# watCals_schmatic.net
KiCad netlist of a schematic drawn in EAGLE
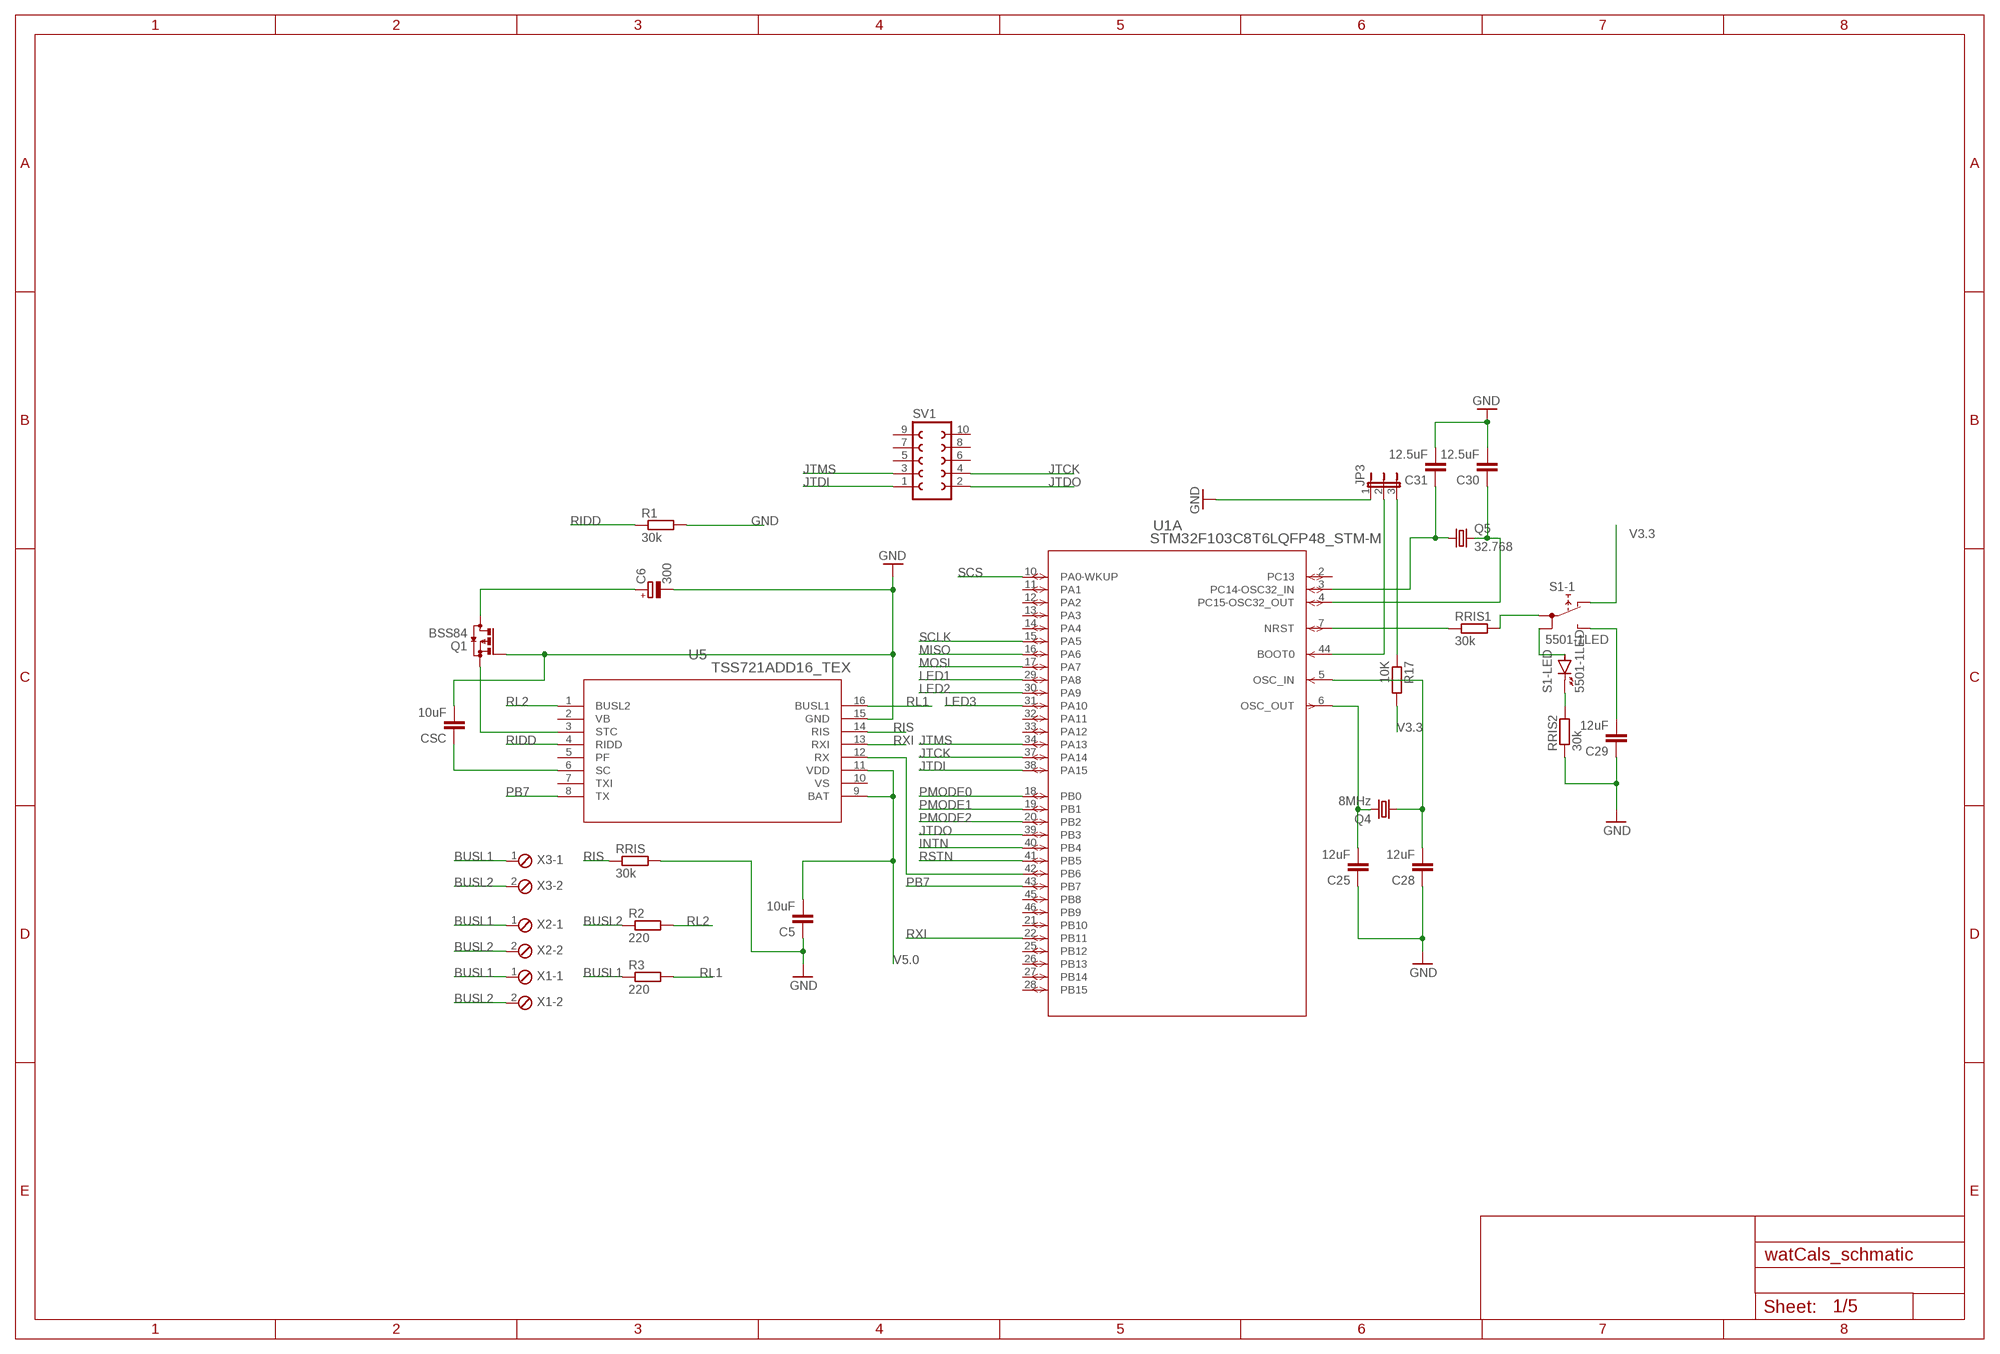
[diagram p0: schematic, sheet 1]
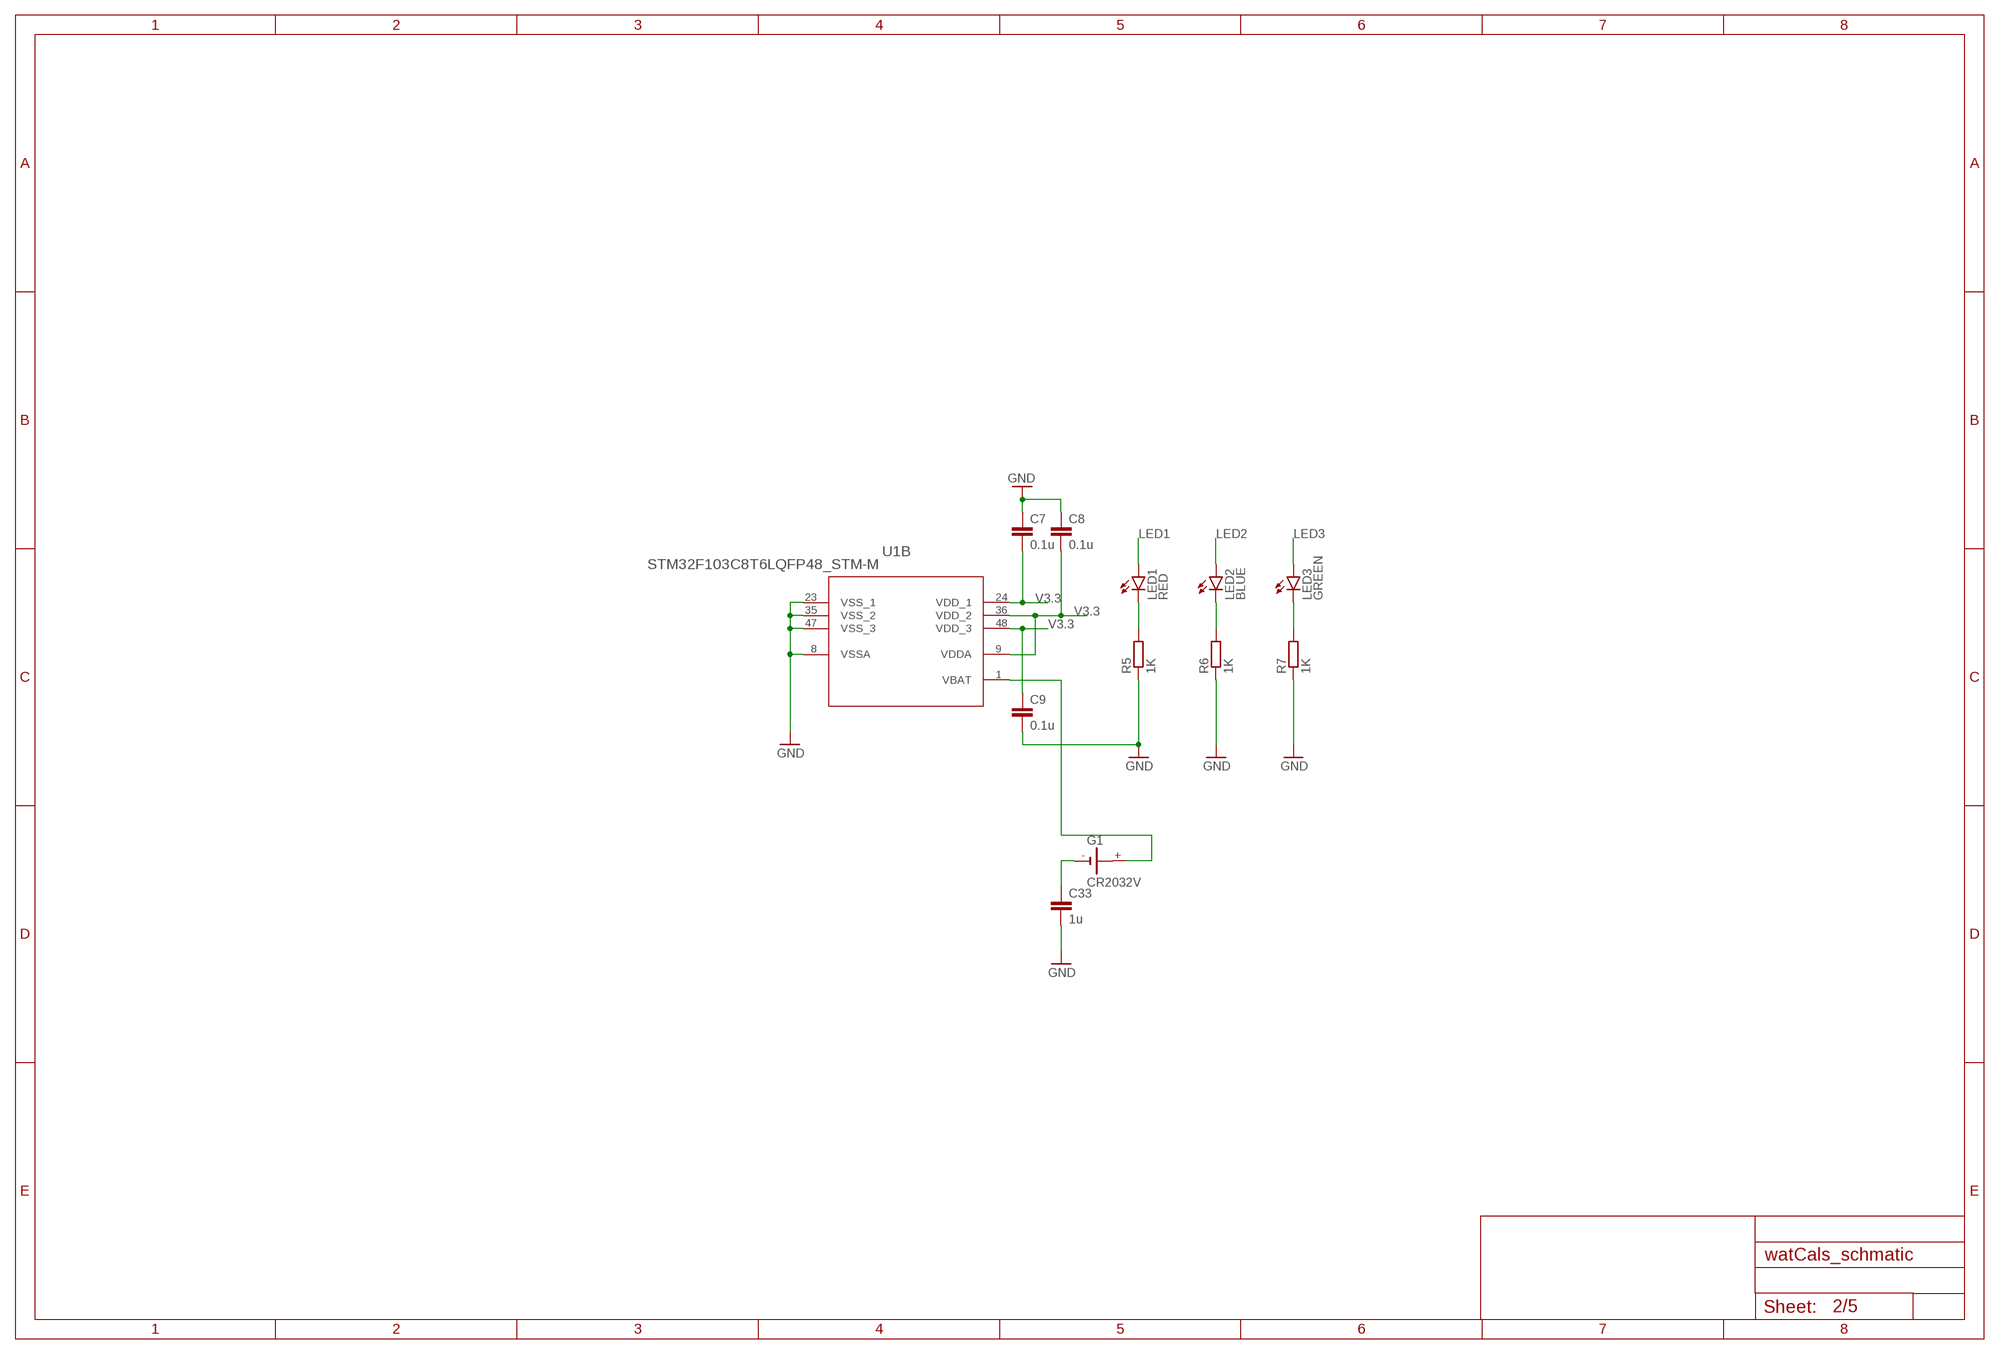
[diagram p1: schematic, sheet 2]
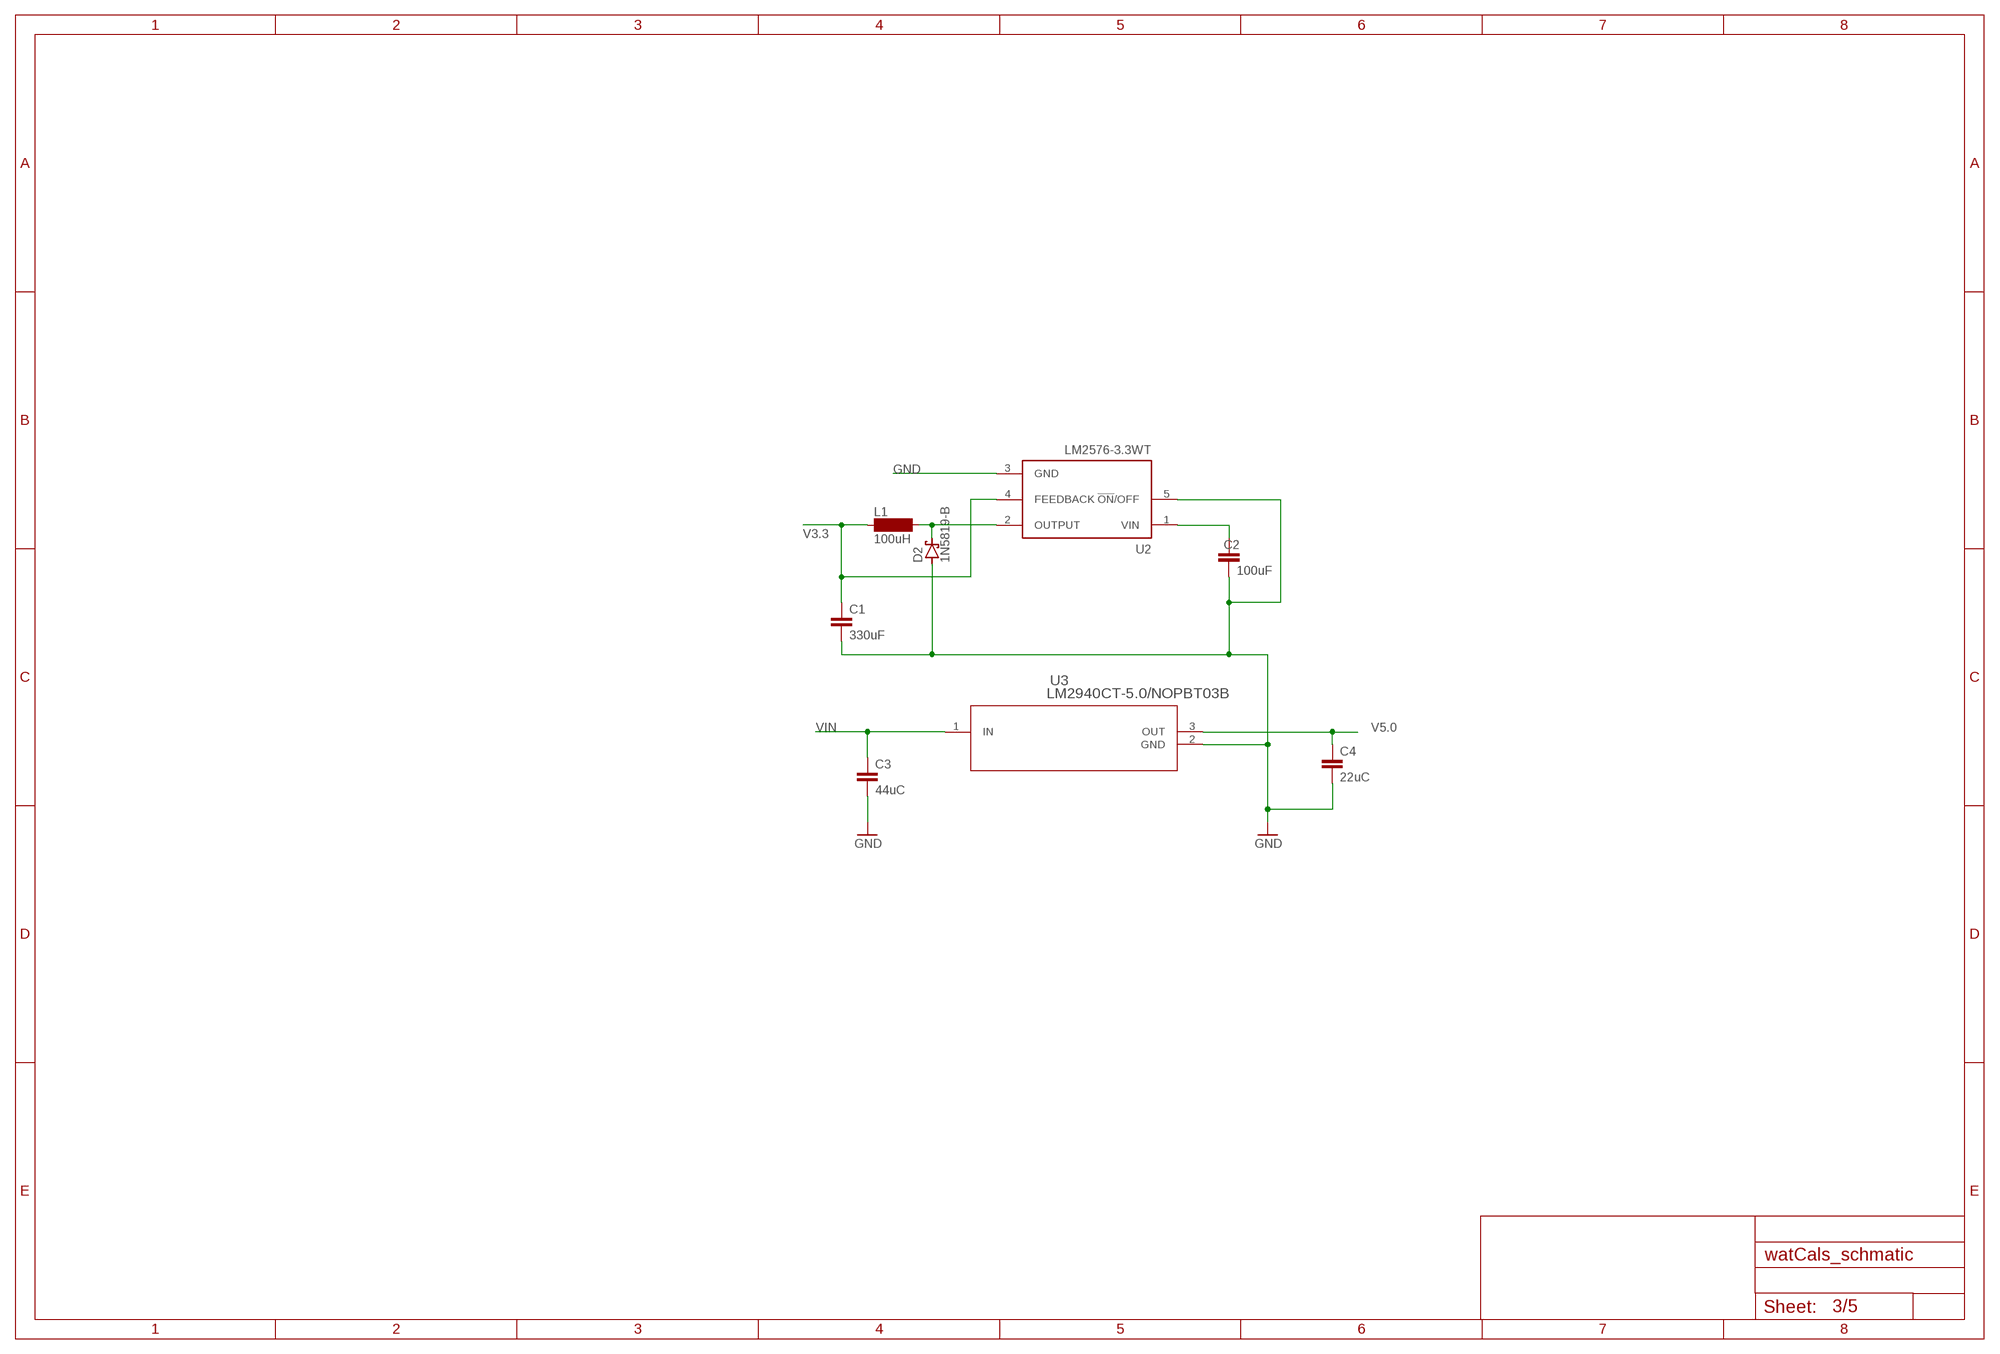
[diagram p2: schematic, sheet 3]
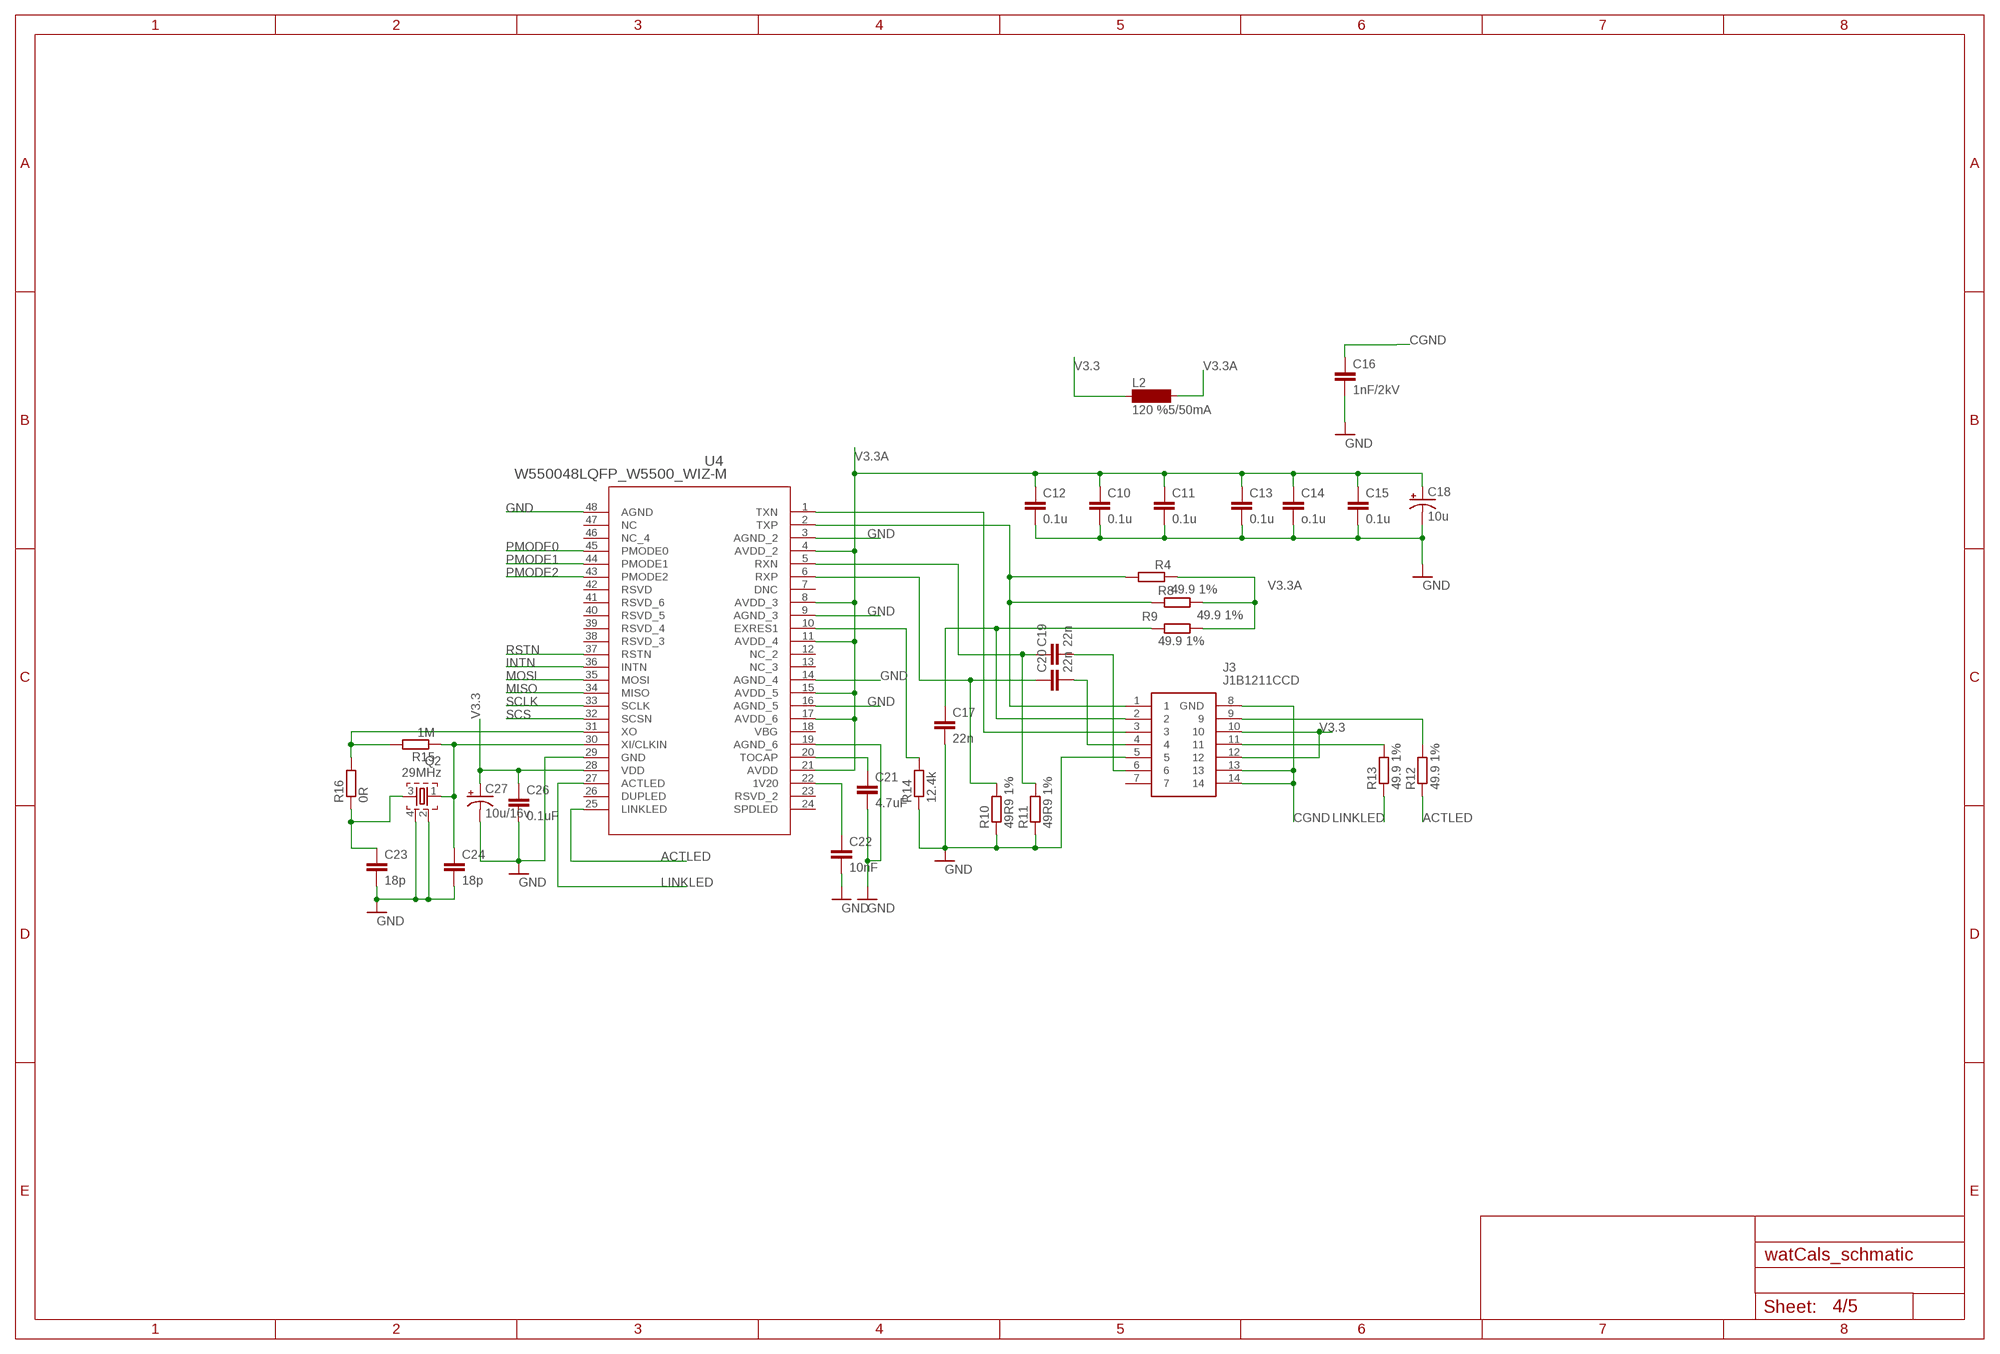
[diagram p3: schematic, sheet 4]
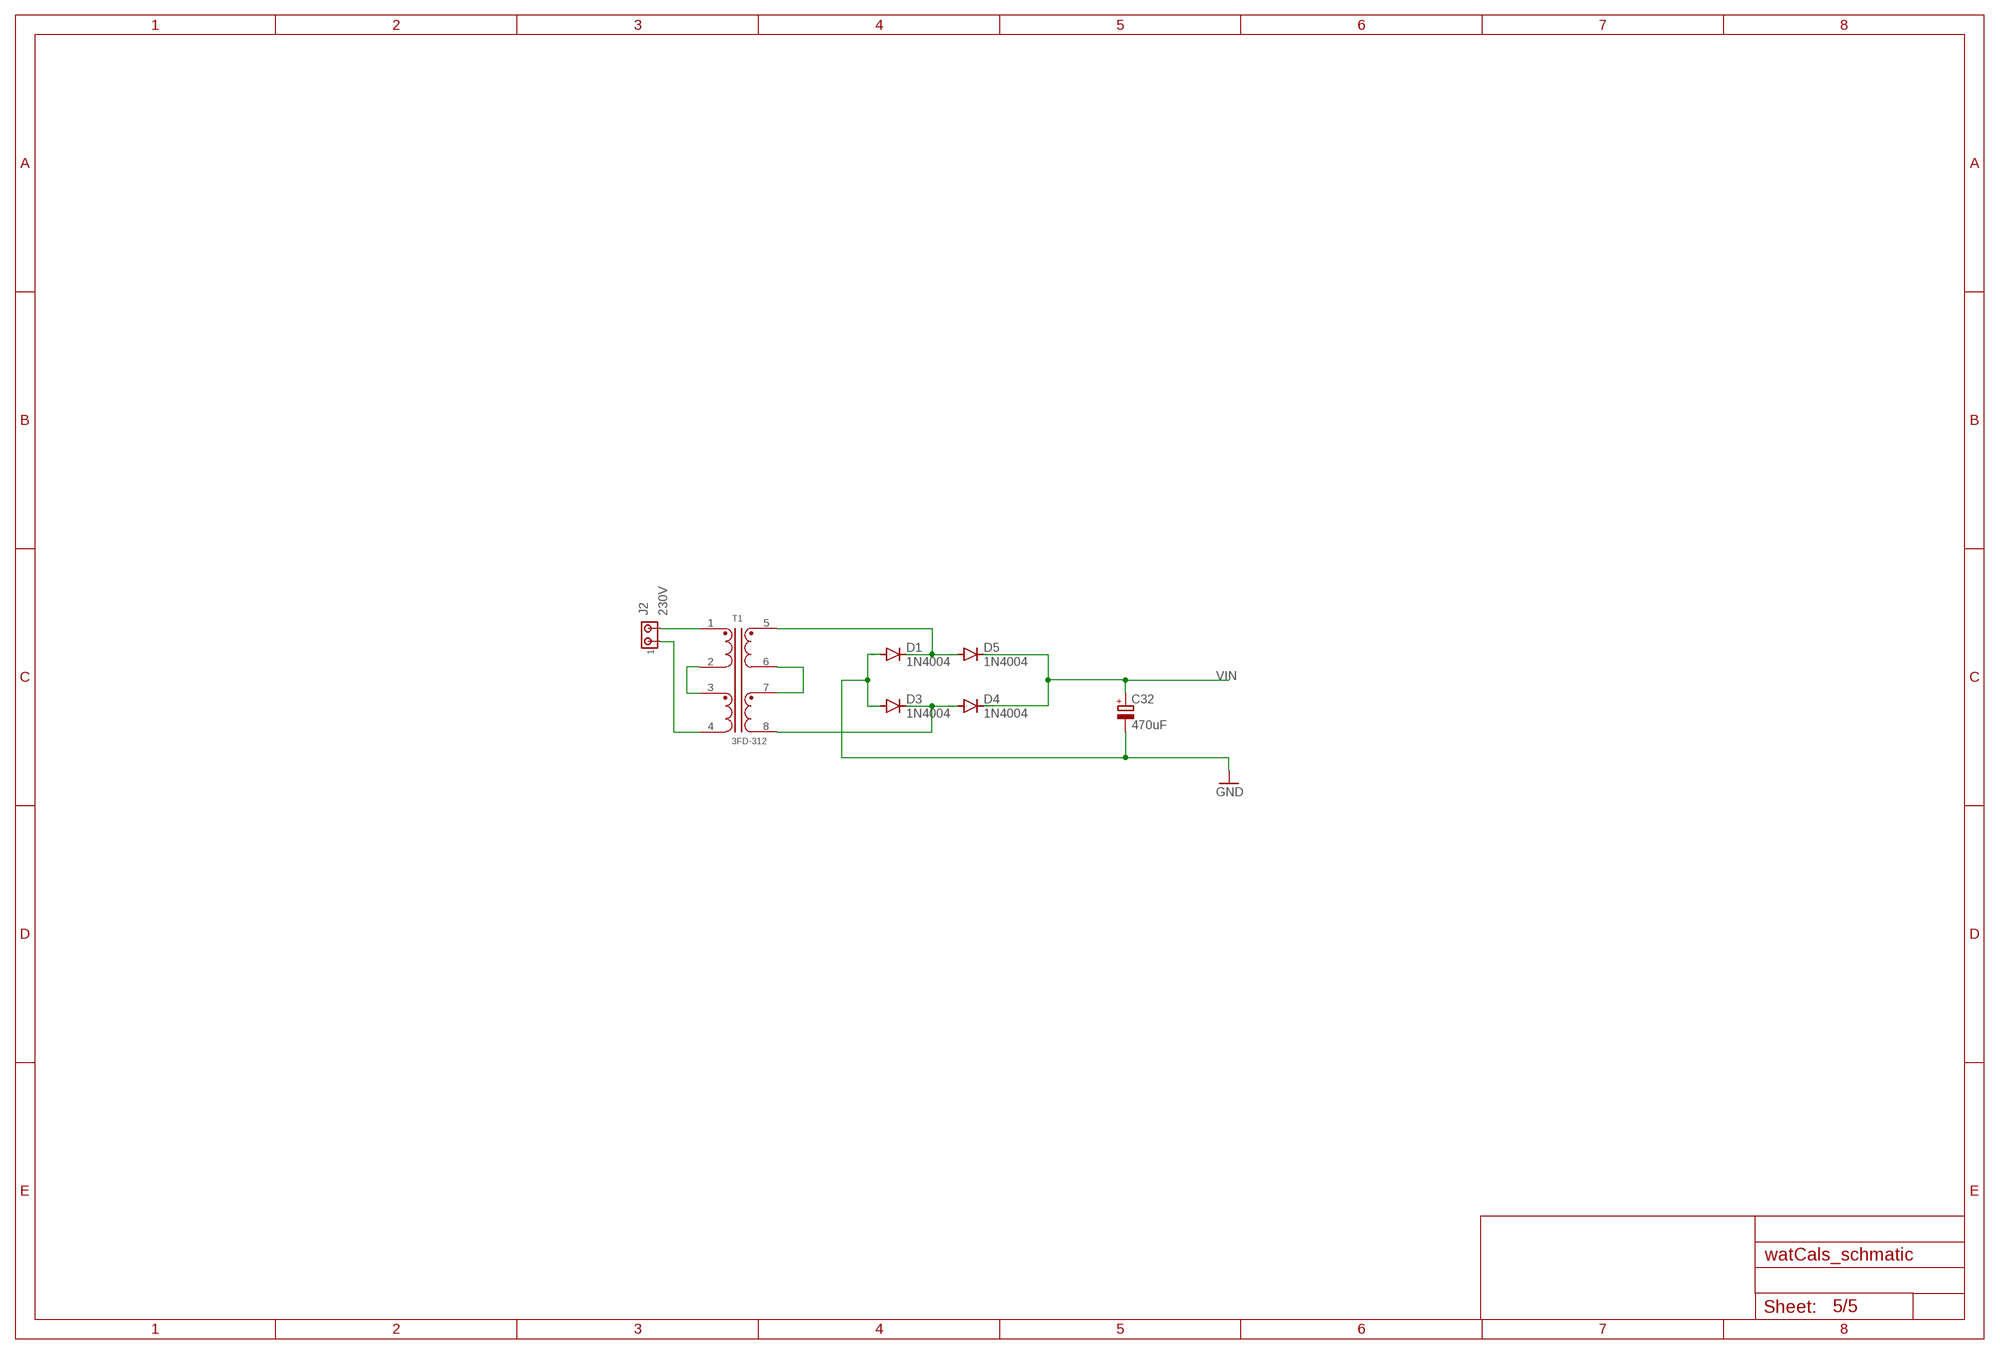
[diagram p4: schematic, sheet 5]

(export (version "E")
  (design (tool "Eeschema 10.0.6"))
  (components
    (comp (ref "C5")
      (value "10uF")
      (footprint "eagle-import:C2.5-2")
      (libsource (lib "eagle-import") (part "C2.5/2"))
    )
    (comp (ref "C6")
      (value "300")
      (footprint "eagle-import:E2,5-6E")
      (libsource (lib "eagle-import") (part "CPOL-EUE2,5-6E"))
    )
    (comp (ref "C25")
      (value "12uF")
      (footprint "eagle-import:C2.5-2")
      (libsource (lib "eagle-import") (part "C2.5/2"))
    )
    (comp (ref "C28")
      (value "12uF")
      (footprint "eagle-import:C2.5-2")
      (libsource (lib "eagle-import") (part "C2.5/2"))
    )
    (comp (ref "C29")
      (value "12uF")
      (footprint "eagle-import:C2.5-2")
      (libsource (lib "eagle-import") (part "C2.5/2"))
    )
    (comp (ref "C30")
      (value "12.5uF")
      (footprint "eagle-import:C2.5-2")
      (libsource (lib "eagle-import") (part "C2.5/2"))
    )
    (comp (ref "C31")
      (value "12.5uF")
      (footprint "eagle-import:C2.5-2")
      (libsource (lib "eagle-import") (part "C2.5/2"))
    )
    (comp (ref "CSC")
      (value "10uF")
      (footprint "eagle-import:C2.5-2")
      (libsource (lib "eagle-import") (part "C2.5/2"))
    )
    (comp (ref "JP3")
      (value "JP2E")
      (footprint "eagle-import:JP2")
      (libsource (lib "eagle-import") (part "JP2E"))
    )
    (comp (ref "Q1")
      (value "BSS84")
      (footprint "eagle-import:SOT23")
      (libsource (lib "eagle-import") (part "BSS84"))
    )
    (comp (ref "Q4")
      (value "8MHz")
      (footprint "eagle-import:HC49_S")
      (libsource (lib "eagle-import") (part "CRYSTALHC49S"))
    )
    (comp (ref "Q5")
      (value "32.768")
      (footprint "eagle-import:FC-12M")
      (libsource (lib "eagle-import") (part "FC-12M"))
    )
    (comp (ref "R1")
      (value "30k")
      (footprint "eagle-import:0207_10")
      (libsource (lib "eagle-import") (part "R-EU_0207/10"))
    )
    (comp (ref "R2")
      (value "220")
      (footprint "eagle-import:0207_10")
      (libsource (lib "eagle-import") (part "R-EU_0207/10"))
    )
    (comp (ref "R3")
      (value "220")
      (footprint "eagle-import:0207_10")
      (libsource (lib "eagle-import") (part "R-EU_0207/10"))
    )
    (comp (ref "R17")
      (value "10K")
      (footprint "eagle-import:0207_10")
      (libsource (lib "eagle-import") (part "R-EU_0207/10"))
    )
    (comp (ref "RRIS")
      (value "30k")
      (footprint "eagle-import:0207_10")
      (libsource (lib "eagle-import") (part "R-EU_0207/10"))
    )
    (comp (ref "RRIS1")
      (value "30k")
      (footprint "eagle-import:0207_10")
      (libsource (lib "eagle-import") (part "R-EU_0207/10"))
    )
    (comp (ref "RRIS2")
      (value "30k")
      (footprint "eagle-import:0207_10")
      (libsource (lib "eagle-import") (part "R-EU_0207/10"))
    )
    (comp (ref "S1")
      (value "5501-1LED")
      (footprint "eagle-import:5501-1LED")
      (libsource (lib "eagle-import") (part "55?-1LED01"))
    )
    (comp (ref "SV1")
      (value "FE05-2")
      (footprint "eagle-import:FE05-2")
      (libsource (lib "eagle-import") (part "FE05-2"))
    )
    (comp (ref "U1")
      (value "STM32F103C8T6LQFP48_STM-M")
      (footprint "eagle-import:LQFP48_STM-M")
      (fields
        (field (name "MANUFACTURER_PART_NUMBER") "STM32F103C8T6")
        (field (name "COPYRIGHT") "Copyright (C) 2024 Ultra Librarian. All rights reserved.")
      )
      (libsource (lib "eagle-import") (part "STM32F103C8T6LQFP48_STM-M"))
    )
    (comp (ref "U5")
      (value "TSS721ADD16_TEX")
      (footprint "eagle-import:D16_TEX")
      (fields
        (field (name "MANUFACTURER_PART_NUMBER") "TSS721AD")
        (field (name "COPYRIGHT") "Copyright (C) 2024 Ultra Librarian. All rights reserved.")
      )
      (libsource (lib "eagle-import") (part "TSS721ADD16_TEX"))
    )
    (comp (ref "X1")
      (value "MPT2")
      (footprint "eagle-import:2POL254")
      (libsource (lib "eagle-import") (part "MPT2"))
    )
    (comp (ref "X2")
      (value "MPT2")
      (footprint "eagle-import:2POL254")
      (libsource (lib "eagle-import") (part "MPT2"))
    )
    (comp (ref "X3")
      (value "MPT2")
      (footprint "eagle-import:2POL254")
      (libsource (lib "eagle-import") (part "MPT2"))
    )
    (comp (ref "C1")
      (value "330uF")
      (footprint "eagle-import:C2.5-2")
      (libsource (lib "eagle-import") (part "C2.5/2"))
    )
    (comp (ref "C2")
      (value "100uF")
      (footprint "eagle-import:C2.5-2")
      (libsource (lib "eagle-import") (part "C2.5/2"))
    )
    (comp (ref "C3")
      (value "44uC")
      (footprint "eagle-import:C2.5-3")
      (libsource (lib "eagle-import") (part "C2,5-3"))
    )
    (comp (ref "C4")
      (value "22uC")
      (footprint "eagle-import:C2.5-3")
      (libsource (lib "eagle-import") (part "C2,5-3"))
    )
    (comp (ref "D2")
      (value "1N5819-B")
      (footprint "eagle-import:DO41-7.6")
      (libsource (lib "eagle-import") (part "1N5819-B"))
    )
    (comp (ref "L1")
      (value "100uH")
      (footprint "eagle-import:SD8")
      (libsource (lib "eagle-import") (part "SD8"))
    )
    (comp (ref "U2")
      (value "LM2576-3.3WT")
      (footprint "eagle-import:TO170P1054X470X1514-5")
      (fields (field (name "MF") "Microchip"))
      (libsource (lib "eagle-import") (part "LM2576-3.3WT"))
    )
    (comp (ref "U3")
      (value "LM2940CT-5.0/NOPBT03B")
      (footprint "eagle-import:T03B")
      (fields
        (field (name "MANUFACTURER_PART_NUMBER") "LM2940CT-5.0/NOPB")
        (field (name "COPYRIGHT") "Copyright (C) 2024 Ultra Librarian. All rights reserved.")
      )
      (libsource (lib "eagle-import") (part "LM2940CT-5.0/NOPBT03B"))
    )
    (comp (ref "C7")
      (value "0.1u")
      (footprint "eagle-import:C2.5-2")
      (libsource (lib "eagle-import") (part "C2.5/2"))
    )
    (comp (ref "C8")
      (value "0.1u")
      (footprint "eagle-import:C2.5-2")
      (libsource (lib "eagle-import") (part "C2.5/2"))
    )
    (comp (ref "C9")
      (value "0.1u")
      (footprint "eagle-import:C2.5-2")
      (libsource (lib "eagle-import") (part "C2.5/2"))
    )
    (comp (ref "C33")
      (value "1u")
      (footprint "eagle-import:C2.5-2")
      (libsource (lib "eagle-import") (part "C2.5/2"))
    )
    (comp (ref "G1")
      (value "CR2032V")
      (footprint "eagle-import:CR2032V")
      (libsource (lib "eagle-import") (part "CR2032V"))
    )
    (comp (ref "LED1")
      (value "RED")
      (footprint "eagle-import:LED5MM")
      (libsource (lib "eagle-import") (part "LED5MM"))
    )
    (comp (ref "LED2")
      (value "BLUE")
      (footprint "eagle-import:LED5MM")
      (libsource (lib "eagle-import") (part "LED5MM"))
    )
    (comp (ref "LED3")
      (value "GREEN")
      (footprint "eagle-import:LED5MM")
      (libsource (lib "eagle-import") (part "LED5MM"))
    )
    (comp (ref "R5")
      (value "1K")
      (footprint "eagle-import:0207_10")
      (libsource (lib "eagle-import") (part "R-EU_0207/10"))
    )
    (comp (ref "R6")
      (value "1K")
      (footprint "eagle-import:0207_10")
      (libsource (lib "eagle-import") (part "R-EU_0207/10"))
    )
    (comp (ref "R7")
      (value "1K")
      (footprint "eagle-import:0207_10")
      (libsource (lib "eagle-import") (part "R-EU_0207/10"))
    )
    (comp (ref "C10")
      (value "0.1u")
      (footprint "eagle-import:C2.5-2")
      (libsource (lib "eagle-import") (part "C2.5/2"))
    )
    (comp (ref "C11")
      (value "0.1u")
      (footprint "eagle-import:C2.5-2")
      (libsource (lib "eagle-import") (part "C2.5/2"))
    )
    (comp (ref "C12")
      (value "0.1u")
      (footprint "eagle-import:C2.5-2")
      (libsource (lib "eagle-import") (part "C2.5/2"))
    )
    (comp (ref "C13")
      (value "0.1u")
      (footprint "eagle-import:C2.5-2")
      (libsource (lib "eagle-import") (part "C2.5/2"))
    )
    (comp (ref "C14")
      (value "o.1u")
      (footprint "eagle-import:C2.5-2")
      (libsource (lib "eagle-import") (part "C2.5/2"))
    )
    (comp (ref "C15")
      (value "0.1u")
      (footprint "eagle-import:C2.5-2")
      (libsource (lib "eagle-import") (part "C2.5/2"))
    )
    (comp (ref "C16")
      (value "1nF/2kV")
      (footprint "eagle-import:C2.5-2")
      (libsource (lib "eagle-import") (part "C2.5/2"))
    )
    (comp (ref "C17")
      (value "22n")
      (footprint "eagle-import:C2.5-2")
      (libsource (lib "eagle-import") (part "C2.5/2"))
    )
    (comp (ref "C18")
      (value "10u")
      (footprint "eagle-import:E2,5-6")
      (libsource (lib "eagle-import") (part "CPOL-USE2.5-6"))
    )
    (comp (ref "C19")
      (value "22n")
      (footprint "eagle-import:C2.5-2")
      (libsource (lib "eagle-import") (part "C2.5/2"))
    )
    (comp (ref "C20")
      (value "22n")
      (footprint "eagle-import:C2.5-2")
      (libsource (lib "eagle-import") (part "C2.5/2"))
    )
    (comp (ref "C21")
      (value "4.7uF")
      (footprint "eagle-import:C2.5-2")
      (libsource (lib "eagle-import") (part "C2.5/2"))
    )
    (comp (ref "C22")
      (value "10nF")
      (footprint "eagle-import:C2.5-2")
      (libsource (lib "eagle-import") (part "C2.5/2"))
    )
    (comp (ref "C23")
      (value "18p")
      (footprint "eagle-import:C2.5-2")
      (libsource (lib "eagle-import") (part "C2.5/2"))
    )
    (comp (ref "C24")
      (value "18p")
      (footprint "eagle-import:C2.5-2")
      (libsource (lib "eagle-import") (part "C2.5/2"))
    )
    (comp (ref "C26")
      (value "0.1uF")
      (footprint "eagle-import:C2.5-2")
      (libsource (lib "eagle-import") (part "C2.5/2"))
    )
    (comp (ref "C27")
      (value "10u/16v")
      (footprint "eagle-import:E2,5-6")
      (libsource (lib "eagle-import") (part "CPOL-USE2.5-6"))
    )
    (comp (ref "J3")
      (value "J1B1211CCD")
      (footprint "eagle-import:J1B1211CCD")
      (libsource (lib "eagle-import") (part "J1B1211CCD"))
    )
    (comp (ref "L2")
      (value "120 %5/50mA")
      (footprint "eagle-import:SD8")
      (libsource (lib "eagle-import") (part "SD8"))
    )
    (comp (ref "Q2")
      (value "29MHz")
      (footprint "eagle-import:FA-20H")
      (libsource (lib "eagle-import") (part "FA-20H"))
    )
    (comp (ref "R4")
      (value "49.9 1%")
      (footprint "eagle-import:0207_10")
      (libsource (lib "eagle-import") (part "R-EU_0207/10"))
    )
    (comp (ref "R8")
      (value "49.9 1%")
      (footprint "eagle-import:0207_10")
      (libsource (lib "eagle-import") (part "R-EU_0207/10"))
    )
    (comp (ref "R9")
      (value "49.9 1%")
      (footprint "eagle-import:0207_10")
      (libsource (lib "eagle-import") (part "R-EU_0207/10"))
    )
    (comp (ref "R10")
      (value "49R9 1%")
      (footprint "eagle-import:0207_10")
      (libsource (lib "eagle-import") (part "R-EU_0207/10"))
    )
    (comp (ref "R11")
      (value "49R9 1%")
      (footprint "eagle-import:0207_10")
      (libsource (lib "eagle-import") (part "R-EU_0207/10"))
    )
    (comp (ref "R12")
      (value "49.9 1%")
      (footprint "eagle-import:0207_10")
      (libsource (lib "eagle-import") (part "R-EU_0207/10"))
    )
    (comp (ref "R13")
      (value "49.9 1%")
      (footprint "eagle-import:0207_10")
      (libsource (lib "eagle-import") (part "R-EU_0207/10"))
    )
    (comp (ref "R14")
      (value "12.4k")
      (footprint "eagle-import:0207_10")
      (libsource (lib "eagle-import") (part "R-EU_0207/10"))
    )
    (comp (ref "R15")
      (value "1M")
      (footprint "eagle-import:0207_10")
      (libsource (lib "eagle-import") (part "R-EU_0207/10"))
    )
    (comp (ref "R16")
      (value "0R")
      (footprint "eagle-import:0207_10")
      (libsource (lib "eagle-import") (part "R-EU_0207/10"))
    )
    (comp (ref "U4")
      (value "W550048LQFP_W5500_WIZ-M")
      (footprint "eagle-import:48LQFP_W5500_WIZ-M")
      (fields
        (field (name "MANUFACTURER_PART_NUMBER") "W5500")
        (field (name "COPYRIGHT") "Copyright (C) 2024 Ultra Librarian. All rights reserved.")
      )
      (libsource (lib "eagle-import") (part "W550048LQFP_W5500_WIZ-M"))
    )
    (comp (ref "C32")
      (value "470uF")
      (footprint "eagle-import:E2,5-6E")
      (libsource (lib "eagle-import") (part "CPOL-EUE2,5-6E"))
    )
    (comp (ref "D1")
      (value "1N4004")
      (footprint "eagle-import:DO41-10")
      (libsource (lib "eagle-import") (part "1N4004"))
    )
    (comp (ref "D3")
      (value "1N4004")
      (footprint "eagle-import:DO41-10")
      (libsource (lib "eagle-import") (part "1N4004"))
    )
    (comp (ref "D4")
      (value "1N4004")
      (footprint "eagle-import:DO41-10")
      (libsource (lib "eagle-import") (part "1N4004"))
    )
    (comp (ref "D5")
      (value "1N4004")
      (footprint "eagle-import:DO41-10")
      (libsource (lib "eagle-import") (part "1N4004"))
    )
    (comp (ref "J2")
      (value "230V")
      (footprint "eagle-import:10X02MTA")
      (libsource (lib "eagle-import") (part "MTA02-100"))
    )
    (comp (ref "T1")
      (value "3FD-312")
      (footprint "eagle-import:XFMR_3FD-312")
      (fields (field (name "MF") "Tamura"))
      (libsource (lib "eagle-import") (part "3FD-312"))
    )
  )
  (nets
    (net (code "1") (name "ACTLED") (class "Default")
      (node (ref "R12") (pin "1") (pinfunction "1_1") (pintype "passive"))
      (node (ref "U4") (pin "25") (pinfunction "LINKLED_25") (pintype "passive"))
    )
    (net (code "2") (name "BUSL1") (class "Default")
      (node (ref "R3") (pin "1") (pinfunction "1_1") (pintype "passive"))
      (node (ref "X1") (pin "1") (pinfunction "1_1") (pintype "passive"))
      (node (ref "X2") (pin "1") (pinfunction "1_1") (pintype "passive"))
      (node (ref "X3") (pin "1") (pinfunction "1_1") (pintype "passive"))
    )
    (net (code "3") (name "BUSL2") (class "Default")
      (node (ref "R2") (pin "1") (pinfunction "1_1") (pintype "passive"))
      (node (ref "X1") (pin "2") (pinfunction "1_2") (pintype "passive"))
      (node (ref "X2") (pin "2") (pinfunction "1_2") (pintype "passive"))
      (node (ref "X3") (pin "2") (pinfunction "1_2") (pintype "passive"))
    )
    (net (code "4") (name "CGND") (class "Default")
      (node (ref "C16") (pin "1") (pinfunction "1_1") (pintype "passive"))
      (node (ref "J3") (pin "13") (pinfunction "13_13") (pintype "bidirectional"))
      (node (ref "J3") (pin "14") (pinfunction "14_14") (pintype "bidirectional"))
      (node (ref "J3") (pin "8") (pinfunction "GND_8") (pintype "bidirectional"))
    )
    (net (code "5") (name "GND") (class "Default")
      (node (ref "C1") (pin "2") (pinfunction "2_2") (pintype "passive"))
      (node (ref "C10") (pin "2") (pinfunction "2_2") (pintype "passive"))
      (node (ref "C11") (pin "2") (pinfunction "2_2") (pintype "passive"))
      (node (ref "C12") (pin "2") (pinfunction "2_2") (pintype "passive"))
      (node (ref "C13") (pin "2") (pinfunction "2_2") (pintype "passive"))
      (node (ref "C14") (pin "2") (pinfunction "2_2") (pintype "passive"))
      (node (ref "C15") (pin "2") (pinfunction "2_2") (pintype "passive"))
      (node (ref "C16") (pin "2") (pinfunction "2_2") (pintype "passive"))
      (node (ref "C17") (pin "2") (pinfunction "2_2") (pintype "passive"))
      (node (ref "C18") (pin "-") (pinfunction "-_-") (pintype "passive"))
      (node (ref "C2") (pin "2") (pinfunction "2_2") (pintype "passive"))
      (node (ref "C21") (pin "2") (pinfunction "2_2") (pintype "passive"))
      (node (ref "C22") (pin "2") (pinfunction "2_2") (pintype "passive"))
      (node (ref "C23") (pin "2") (pinfunction "2_2") (pintype "passive"))
      (node (ref "C24") (pin "2") (pinfunction "2_2") (pintype "passive"))
      (node (ref "C25") (pin "1") (pinfunction "1_1") (pintype "passive"))
      (node (ref "C26") (pin "2") (pinfunction "2_2") (pintype "passive"))
      (node (ref "C27") (pin "-") (pinfunction "-_-") (pintype "passive"))
      (node (ref "C28") (pin "1") (pinfunction "1_1") (pintype "passive"))
      (node (ref "C29") (pin "1") (pinfunction "1_1") (pintype "passive"))
      (node (ref "C3") (pin "2") (pinfunction "2_2") (pintype "passive"))
      (node (ref "C30") (pin "2") (pinfunction "2_2") (pintype "passive"))
      (node (ref "C31") (pin "2") (pinfunction "2_2") (pintype "passive"))
      (node (ref "C32") (pin "-") (pinfunction "-_-") (pintype "passive"))
      (node (ref "C33") (pin "2") (pinfunction "2_2") (pintype "passive"))
      (node (ref "C4") (pin "2") (pinfunction "2_2") (pintype "passive"))
      (node (ref "C5") (pin "1") (pinfunction "1_1") (pintype "passive"))
      (node (ref "C6") (pin "-") (pinfunction "-_-") (pintype "passive"))
      (node (ref "C7") (pin "1") (pinfunction "1_1") (pintype "passive"))
      (node (ref "C8") (pin "1") (pinfunction "1_1") (pintype "passive"))
      (node (ref "C9") (pin "2") (pinfunction "2_2") (pintype "passive"))
      (node (ref "CSC") (pin "2") (pinfunction "2_2") (pintype "passive"))
      (node (ref "D1") (pin "A") (pinfunction "A_A") (pintype "passive"))
      (node (ref "D2") (pin "A") (pinfunction "A_A") (pintype "passive"))
      (node (ref "D3") (pin "A") (pinfunction "A_A") (pintype "passive"))
      (node (ref "J3") (pin "5") (pinfunction "5_5") (pintype "bidirectional"))
      (node (ref "JP3") (pin "1") (pinfunction "1_1") (pintype "passive"))
      (node (ref "Q1") (pin "1") (pinfunction "G_1") (pintype "passive"))
      (node (ref "Q2") (pin "2") (pinfunction "2_2") (pintype "passive"))
      (node (ref "Q2") (pin "4") (pinfunction "4_4") (pintype "passive"))
      (node (ref "R1") (pin "2") (pinfunction "2_2") (pintype "passive"))
      (node (ref "R10") (pin "1") (pinfunction "1_1") (pintype "passive"))
      (node (ref "R11") (pin "1") (pinfunction "1_1") (pintype "passive"))
      (node (ref "R14") (pin "1") (pinfunction "1_1") (pintype "passive"))
      (node (ref "R5") (pin "1") (pinfunction "1_1") (pintype "passive"))
      (node (ref "R6") (pin "1") (pinfunction "1_1") (pintype "passive"))
      (node (ref "R7") (pin "1") (pinfunction "1_1") (pintype "passive"))
      (node (ref "RRIS") (pin "2") (pinfunction "2_2") (pintype "passive"))
      (node (ref "RRIS2") (pin "1") (pinfunction "1_1") (pintype "passive"))
      (node (ref "U1") (pin "23") (pinfunction "VSS_1_23") (pintype "power_in"))
      (node (ref "U1") (pin "35") (pinfunction "VSS_2_35") (pintype "power_in"))
      (node (ref "U1") (pin "47") (pinfunction "VSS_3_47") (pintype "power_in"))
      (node (ref "U1") (pin "8") (pinfunction "VSSA_8") (pintype "power_in"))
      (node (ref "U2") (pin "3") (pinfunction "GND_3") (pintype "power_in"))
      (node (ref "U2") (pin "5") (pinfunction "~{ON}/OFF_5") (pintype "input"))
      (node (ref "U3") (pin "2") (pinfunction "GND_2") (pintype "passive"))
      (node (ref "U4") (pin "14") (pinfunction "AGND_4_14") (pintype "passive"))
      (node (ref "U4") (pin "16") (pinfunction "AGND_5_16") (pintype "passive"))
      (node (ref "U4") (pin "19") (pinfunction "AGND_6_19") (pintype "passive"))
      (node (ref "U4") (pin "29") (pinfunction "GND_29") (pintype "passive"))
      (node (ref "U4") (pin "3") (pinfunction "AGND_2_3") (pintype "passive"))
      (node (ref "U4") (pin "48") (pinfunction "AGND_48") (pintype "passive"))
      (node (ref "U4") (pin "9") (pinfunction "AGND_3_9") (pintype "passive"))
      (node (ref "U5") (pin "15") (pinfunction "GND_15") (pintype "power_in"))
    )
    (net (code "6") (name "INTN") (class "Default")
      (node (ref "U1") (pin "40") (pinfunction "PB4_40") (pintype "bidirectional"))
      (node (ref "U4") (pin "36") (pinfunction "INTN_36") (pintype "passive"))
    )
    (net (code "7") (name "JTCK") (class "Default")
      (node (ref "SV1") (pin "4") (pinfunction "4_4") (pintype "passive"))
      (node (ref "U1") (pin "37") (pinfunction "PA14_37") (pintype "bidirectional"))
    )
    (net (code "8") (name "JTDI") (class "Default")
      (node (ref "SV1") (pin "1") (pinfunction "1_1") (pintype "passive"))
      (node (ref "U1") (pin "38") (pinfunction "PA15_38") (pintype "bidirectional"))
    )
    (net (code "9") (name "JTDO") (class "Default")
      (node (ref "SV1") (pin "2") (pinfunction "2_2") (pintype "passive"))
      (node (ref "U1") (pin "39") (pinfunction "PB3_39") (pintype "bidirectional"))
    )
    (net (code "10") (name "JTMS") (class "Default")
      (node (ref "SV1") (pin "3") (pinfunction "3_3") (pintype "passive"))
      (node (ref "U1") (pin "34") (pinfunction "PA13_34") (pintype "bidirectional"))
    )
    (net (code "11") (name "LED1") (class "Default")
      (node (ref "LED1") (pin "A") (pinfunction "A_A") (pintype "passive"))
      (node (ref "U1") (pin "29") (pinfunction "PA8_29") (pintype "bidirectional"))
    )
    (net (code "12") (name "LED2") (class "Default")
      (node (ref "LED2") (pin "A") (pinfunction "A_A") (pintype "passive"))
      (node (ref "U1") (pin "30") (pinfunction "PA9_30") (pintype "bidirectional"))
    )
    (net (code "13") (name "LED3") (class "Default")
      (node (ref "LED3") (pin "A") (pinfunction "A_A") (pintype "passive"))
      (node (ref "U1") (pin "31") (pinfunction "PA10_31") (pintype "bidirectional"))
    )
    (net (code "14") (name "LINKLED") (class "Default")
      (node (ref "R13") (pin "1") (pinfunction "1_1") (pintype "passive"))
      (node (ref "U4") (pin "27") (pinfunction "ACTLED_27") (pintype "passive"))
    )
    (net (code "15") (name "MISO") (class "Default")
      (node (ref "U1") (pin "16") (pinfunction "PA6_16") (pintype "bidirectional"))
      (node (ref "U4") (pin "34") (pinfunction "MISO_34") (pintype "passive"))
    )
    (net (code "16") (name "MOSI") (class "Default")
      (node (ref "U1") (pin "17") (pinfunction "PA7_17") (pintype "bidirectional"))
      (node (ref "U4") (pin "35") (pinfunction "MOSI_35") (pintype "passive"))
    )
    (net (code "17") (name "Net-(C17-Pad1)") (class "Default")
      (node (ref "C17") (pin "1") (pinfunction "1_1") (pintype "passive"))
      (node (ref "J3") (pin "2") (pinfunction "2_2") (pintype "bidirectional"))
      (node (ref "R9") (pin "1") (pinfunction "1_1") (pintype "passive"))
    )
    (net (code "18") (name "Net-(C19-Pad2)") (class "Default")
      (node (ref "C19") (pin "2") (pinfunction "2_2") (pintype "passive"))
      (node (ref "J3") (pin "6") (pinfunction "6_6") (pintype "bidirectional"))
    )
    (net (code "19") (name "Net-(C20-Pad2)") (class "Default")
      (node (ref "C20") (pin "2") (pinfunction "2_2") (pintype "passive"))
      (node (ref "J3") (pin "4") (pinfunction "4_4") (pintype "bidirectional"))
    )
    (net (code "20") (name "Net-(C23-Pad1)") (class "Default")
      (node (ref "C23") (pin "1") (pinfunction "1_1") (pintype "passive"))
      (node (ref "Q2") (pin "3") (pinfunction "3_3") (pintype "passive"))
      (node (ref "R16") (pin "1") (pinfunction "1_1") (pintype "passive"))
    )
    (net (code "21") (name "Net-(C29-Pad2)") (class "Default")
      (node (ref "C29") (pin "2") (pinfunction "2_2") (pintype "passive"))
      (node (ref "S1") (pin "NO") (pinfunction "NO_NO") (pintype "passive"))
    )
    (net (code "22") (name "Net-(C33-Pad1)") (class "Default")
      (node (ref "C33") (pin "1") (pinfunction "1_1") (pintype "passive"))
      (node (ref "G1") (pin "-") (pinfunction "-_-") (pintype "passive"))
    )
    (net (code "23") (name "Net-(D1-PadC)") (class "Default")
      (node (ref "D1") (pin "C") (pinfunction "C_C") (pintype "passive"))
      (node (ref "D5") (pin "A") (pinfunction "A_A") (pintype "passive"))
      (node (ref "T1") (pin "5") (pinfunction "5_5") (pintype "passive"))
    )
    (net (code "24") (name "Net-(D3-PadC)") (class "Default")
      (node (ref "D3") (pin "C") (pinfunction "C_C") (pintype "passive"))
      (node (ref "D4") (pin "A") (pinfunction "A_A") (pintype "passive"))
      (node (ref "T1") (pin "8") (pinfunction "8_8") (pintype "passive"))
    )
    (net (code "25") (name "Net-(J2-Pad1)") (class "Default")
      (node (ref "J2") (pin "1") (pinfunction "1_1") (pintype "passive"))
      (node (ref "T1") (pin "4") (pinfunction "4_4") (pintype "passive"))
    )
    (net (code "26") (name "Net-(J2-Pad2)") (class "Default")
      (node (ref "J2") (pin "2") (pinfunction "2_2") (pintype "passive"))
      (node (ref "T1") (pin "1") (pinfunction "1_1") (pintype "passive"))
    )
    (net (code "27") (name "Net-(J3-Pad9)") (class "Default")
      (node (ref "J3") (pin "9") (pinfunction "9_9") (pintype "bidirectional"))
      (node (ref "R12") (pin "2") (pinfunction "2_2") (pintype "passive"))
    )
    (net (code "28") (name "Net-(J3-Pad11)") (class "Default")
      (node (ref "J3") (pin "11") (pinfunction "11_11") (pintype "bidirectional"))
      (node (ref "R13") (pin "2") (pinfunction "2_2") (pintype "passive"))
    )
    (net (code "29") (name "Net-(JP3-Pad3)") (class "Default")
      (node (ref "JP3") (pin "3") (pinfunction "3_3") (pintype "passive"))
      (node (ref "R17") (pin "1") (pinfunction "1_1") (pintype "passive"))
    )
    (net (code "30") (name "Net-(LED1-C)") (class "Default")
      (node (ref "LED1") (pin "K") (pinfunction "C_K") (pintype "passive"))
      (node (ref "R5") (pin "2") (pinfunction "2_2") (pintype "passive"))
    )
    (net (code "31") (name "Net-(LED2-C)") (class "Default")
      (node (ref "LED2") (pin "K") (pinfunction "C_K") (pintype "passive"))
      (node (ref "R6") (pin "2") (pinfunction "2_2") (pintype "passive"))
    )
    (net (code "32") (name "Net-(LED3-C)") (class "Default")
      (node (ref "LED3") (pin "K") (pinfunction "C_K") (pintype "passive"))
      (node (ref "R7") (pin "2") (pinfunction "2_2") (pintype "passive"))
    )
    (net (code "33") (name "Net-(Q1-D)") (class "Default")
      (node (ref "C6") (pin "+") (pinfunction "+_+") (pintype "passive"))
      (node (ref "Q1") (pin "3") (pinfunction "D_3") (pintype "passive"))
    )
    (net (code "34") (name "Net-(Q1-S)") (class "Default")
      (node (ref "Q1") (pin "2") (pinfunction "S_2") (pintype "passive"))
      (node (ref "U5") (pin "3") (pinfunction "STC_3") (pintype "passive"))
    )
    (net (code "35") (name "Net-(RRIS1-Pad2)") (class "Default")
      (node (ref "RRIS1") (pin "2") (pinfunction "2_2") (pintype "passive"))
      (node (ref "S1") (pin "1A") (pinfunction "1A_1A") (pintype "passive"))
    )
    (net (code "36") (name "Net-(S1B-A)") (class "Default")
      (node (ref "S1") (pin "+") (pinfunction "A_+") (pintype "passive"))
      (node (ref "S1") (pin "1B") (pinfunction "1B_1B") (pintype "passive"))
    )
    (net (code "37") (name "Net-(S1B-K)") (class "Default")
      (node (ref "RRIS2") (pin "2") (pinfunction "2_2") (pintype "passive"))
      (node (ref "S1") (pin "-") (pinfunction "K_-") (pintype "passive"))
    )
    (net (code "38") (name "Net-(T1-Pad2)") (class "Default")
      (node (ref "T1") (pin "2") (pinfunction "2_2") (pintype "passive"))
      (node (ref "T1") (pin "3") (pinfunction "3_3") (pintype "passive"))
    )
    (net (code "39") (name "Net-(T1-Pad6)") (class "Default")
      (node (ref "T1") (pin "6") (pinfunction "6_6") (pintype "passive"))
      (node (ref "T1") (pin "7") (pinfunction "7_7") (pintype "passive"))
    )
    (net (code "40") (name "Net-(U1A-BOOT0)") (class "Default")
      (node (ref "JP3") (pin "2") (pinfunction "2_2") (pintype "passive"))
      (node (ref "U1") (pin "44") (pinfunction "BOOT0_44") (pintype "input"))
    )
    (net (code "41") (name "Net-(U1A-NRST)") (class "Default")
      (node (ref "RRIS1") (pin "1") (pinfunction "1_1") (pintype "passive"))
      (node (ref "U1") (pin "7") (pinfunction "NRST_7") (pintype "bidirectional"))
    )
    (net (code "42") (name "Net-(U1A-OSC_IN)") (class "Default")
      (node (ref "C28") (pin "2") (pinfunction "2_2") (pintype "passive"))
      (node (ref "Q4") (pin "1") (pinfunction "1_1") (pintype "passive"))
      (node (ref "U1") (pin "5") (pinfunction "OSC_IN_5") (pintype "input"))
    )
    (net (code "43") (name "Net-(U1A-OSC_OUT)") (class "Default")
      (node (ref "C25") (pin "2") (pinfunction "2_2") (pintype "passive"))
      (node (ref "Q4") (pin "2") (pinfunction "2_2") (pintype "passive"))
      (node (ref "U1") (pin "6") (pinfunction "OSC_OUT_6") (pintype "output"))
    )
    (net (code "44") (name "Net-(U1A-PB6)") (class "Default")
      (node (ref "U1") (pin "42") (pinfunction "PB6_42") (pintype "bidirectional"))
      (node (ref "U5") (pin "12") (pinfunction "RX_12") (pintype "input"))
    )
    (net (code "45") (name "Net-(U1A-PC14-OSC32_IN)") (class "Default")
      (node (ref "C31") (pin "1") (pinfunction "1_1") (pintype "passive"))
      (node (ref "Q5") (pin "1") (pinfunction "1_1") (pintype "passive"))
      (node (ref "U1") (pin "3") (pinfunction "PC14-OSC32_IN_3") (pintype "bidirectional"))
    )
    (net (code "46") (name "Net-(U1A-PC15-OSC32_OUT)") (class "Default")
      (node (ref "C30") (pin "1") (pinfunction "1_1") (pintype "passive"))
      (node (ref "Q5") (pin "2") (pinfunction "2_2") (pintype "passive"))
      (node (ref "U1") (pin "4") (pinfunction "PC15-OSC32_OUT_4") (pintype "bidirectional"))
    )
    (net (code "47") (name "Net-(U1B-VBAT)") (class "Default")
      (node (ref "G1") (pin "+") (pinfunction "+_+") (pintype "passive"))
      (node (ref "U1") (pin "1") (pinfunction "VBAT_1") (pintype "power_in"))
    )
    (net (code "48") (name "Net-(U2-OUTPUT)") (class "Default")
      (node (ref "D2") (pin "C") (pinfunction "C_C") (pintype "passive"))
      (node (ref "L1") (pin "2") (pinfunction "2_2") (pintype "passive"))
      (node (ref "U2") (pin "2") (pinfunction "OUTPUT_2") (pintype "output"))
    )
    (net (code "49") (name "Net-(U2-VIN)") (class "Default")
      (node (ref "C2") (pin "1") (pinfunction "1_1") (pintype "passive"))
      (node (ref "U2") (pin "1") (pinfunction "VIN_1") (pintype "input"))
    )
    (net (code "50") (name "Net-(U4-1V20)") (class "Default")
      (node (ref "C22") (pin "1") (pinfunction "1_1") (pintype "passive"))
      (node (ref "U4") (pin "22") (pinfunction "1V20_22") (pintype "passive"))
    )
    (net (code "51") (name "Net-(U4-EXRES1)") (class "Default")
      (node (ref "R14") (pin "2") (pinfunction "2_2") (pintype "passive"))
      (node (ref "U4") (pin "10") (pinfunction "EXRES1_10") (pintype "passive"))
    )
    (net (code "52") (name "Net-(U4-RXN)") (class "Default")
      (node (ref "C19") (pin "1") (pinfunction "1_1") (pintype "passive"))
      (node (ref "R11") (pin "2") (pinfunction "2_2") (pintype "passive"))
      (node (ref "U4") (pin "5") (pinfunction "RXN_5") (pintype "passive"))
    )
    (net (code "53") (name "Net-(U4-RXP)") (class "Default")
      (node (ref "C20") (pin "1") (pinfunction "1_1") (pintype "passive"))
      (node (ref "R10") (pin "2") (pinfunction "2_2") (pintype "passive"))
      (node (ref "U4") (pin "6") (pinfunction "RXP_6") (pintype "passive"))
    )
    (net (code "54") (name "Net-(U4-TOCAP)") (class "Default")
      (node (ref "C21") (pin "1") (pinfunction "1_1") (pintype "passive"))
      (node (ref "U4") (pin "20") (pinfunction "TOCAP_20") (pintype "passive"))
    )
    (net (code "55") (name "Net-(U4-TXN)") (class "Default")
      (node (ref "J3") (pin "3") (pinfunction "3_3") (pintype "bidirectional"))
      (node (ref "U4") (pin "1") (pinfunction "TXN_1") (pintype "passive"))
    )
    (net (code "56") (name "Net-(U4-TXP)") (class "Default")
      (node (ref "J3") (pin "1") (pinfunction "1_1") (pintype "bidirectional"))
      (node (ref "R4") (pin "2") (pinfunction "2_2") (pintype "passive"))
      (node (ref "R8") (pin "1") (pinfunction "1_1") (pintype "passive"))
      (node (ref "U4") (pin "2") (pinfunction "TXP_2") (pintype "passive"))
    )
    (net (code "57") (name "Net-(U4-XI{slash}CLKIN)") (class "Default")
      (node (ref "C24") (pin "1") (pinfunction "1_1") (pintype "passive"))
      (node (ref "Q2") (pin "1") (pinfunction "1_1") (pintype "passive"))
      (node (ref "R15") (pin "1") (pinfunction "1_1") (pintype "passive"))
      (node (ref "U4") (pin "30") (pinfunction "XI/CLKIN_30") (pintype "passive"))
    )
    (net (code "58") (name "Net-(U4-XO)") (class "Default")
      (node (ref "R15") (pin "2") (pinfunction "2_2") (pintype "passive"))
      (node (ref "R16") (pin "2") (pinfunction "2_2") (pintype "passive"))
      (node (ref "U4") (pin "31") (pinfunction "XO_31") (pintype "passive"))
    )
    (net (code "59") (name "Net-(U5-SC)") (class "Default")
      (node (ref "CSC") (pin "1") (pinfunction "1_1") (pintype "passive"))
      (node (ref "U5") (pin "6") (pinfunction "SC_6") (pintype "passive"))
    )
    (net (code "60") (name "PB7") (class "Default")
      (node (ref "U1") (pin "43") (pinfunction "PB7_43") (pintype "bidirectional"))
      (node (ref "U5") (pin "8") (pinfunction "TX_8") (pintype "output"))
    )
    (net (code "61") (name "PMODE0") (class "Default")
      (node (ref "U1") (pin "18") (pinfunction "PB0_18") (pintype "bidirectional"))
      (node (ref "U4") (pin "45") (pinfunction "PMODE0_45") (pintype "bidirectional"))
    )
    (net (code "62") (name "PMODE1") (class "Default")
      (node (ref "U1") (pin "19") (pinfunction "PB1_19") (pintype "bidirectional"))
      (node (ref "U4") (pin "44") (pinfunction "PMODE1_44") (pintype "bidirectional"))
    )
    (net (code "63") (name "PMODE2") (class "Default")
      (node (ref "U1") (pin "20") (pinfunction "PB2_20") (pintype "bidirectional"))
      (node (ref "U4") (pin "43") (pinfunction "PMODE2_43") (pintype "bidirectional"))
    )
    (net (code "64") (name "RIDD") (class "Default")
      (node (ref "R1") (pin "1") (pinfunction "1_1") (pintype "passive"))
      (node (ref "U5") (pin "4") (pinfunction "RIDD_4") (pintype "input"))
    )
    (net (code "65") (name "RIS") (class "Default")
      (node (ref "RRIS") (pin "1") (pinfunction "1_1") (pintype "passive"))
      (node (ref "U5") (pin "14") (pinfunction "RIS_14") (pintype "input"))
    )
    (net (code "66") (name "RL1") (class "Default")
      (node (ref "R3") (pin "2") (pinfunction "2_2") (pintype "passive"))
      (node (ref "U5") (pin "16") (pinfunction "BUSL1_16") (pintype "passive"))
    )
    (net (code "67") (name "RL2") (class "Default")
      (node (ref "R2") (pin "2") (pinfunction "2_2") (pintype "passive"))
      (node (ref "U5") (pin "1") (pinfunction "BUSL2_1") (pintype "passive"))
    )
    (net (code "68") (name "RSTN") (class "Default")
      (node (ref "U1") (pin "41") (pinfunction "PB5_41") (pintype "bidirectional"))
      (node (ref "U4") (pin "37") (pinfunction "RSTN_37") (pintype "passive"))
    )
    (net (code "69") (name "RXI") (class "Default")
      (node (ref "U1") (pin "22") (pinfunction "PB11_22") (pintype "bidirectional"))
      (node (ref "U5") (pin "13") (pinfunction "RXI_13") (pintype "input"))
    )
    (net (code "70") (name "SCLK") (class "Default")
      (node (ref "U1") (pin "15") (pinfunction "PA5_15") (pintype "bidirectional"))
      (node (ref "U4") (pin "33") (pinfunction "SCLK_33") (pintype "passive"))
    )
    (net (code "71") (name "SCS") (class "Default")
      (node (ref "U1") (pin "10") (pinfunction "PA0-WKUP_10") (pintype "bidirectional"))
      (node (ref "U4") (pin "32") (pinfunction "SCSN_32") (pintype "passive"))
    )
    (net (code "72") (name "V3.3") (class "Default")
      (node (ref "C1") (pin "1") (pinfunction "1_1") (pintype "passive"))
      (node (ref "C26") (pin "1") (pinfunction "1_1") (pintype "passive"))
      (node (ref "C27") (pin "+") (pinfunction "+_+") (pintype "passive"))
      (node (ref "C7") (pin "2") (pinfunction "2_2") (pintype "passive"))
      (node (ref "C8") (pin "2") (pinfunction "2_2") (pintype "passive"))
      (node (ref "C9") (pin "1") (pinfunction "1_1") (pintype "passive"))
      (node (ref "J3") (pin "10") (pinfunction "10_10") (pintype "bidirectional"))
      (node (ref "J3") (pin "12") (pinfunction "12_12") (pintype "bidirectional"))
      (node (ref "L1") (pin "1") (pinfunction "1_1") (pintype "passive"))
      (node (ref "L2") (pin "1") (pinfunction "1_1") (pintype "passive"))
      (node (ref "R17") (pin "2") (pinfunction "2_2") (pintype "passive"))
      (node (ref "S1") (pin "NC") (pinfunction "NC_NC") (pintype "passive"))
      (node (ref "U1") (pin "24") (pinfunction "VDD_1_24") (pintype "power_in"))
      (node (ref "U1") (pin "36") (pinfunction "VDD_2_36") (pintype "power_in"))
      (node (ref "U1") (pin "48") (pinfunction "VDD_3_48") (pintype "power_in"))
      (node (ref "U1") (pin "9") (pinfunction "VDDA_9") (pintype "power_in"))
      (node (ref "U2") (pin "4") (pinfunction "FEEDBACK_4") (pintype "input"))
      (node (ref "U4") (pin "28") (pinfunction "VDD_28") (pintype "power_in"))
    )
    (net (code "73") (name "V3.3A") (class "Default")
      (node (ref "C10") (pin "1") (pinfunction "1_1") (pintype "passive"))
      (node (ref "C11") (pin "1") (pinfunction "1_1") (pintype "passive"))
      (node (ref "C12") (pin "1") (pinfunction "1_1") (pintype "passive"))
      (node (ref "C13") (pin "1") (pinfunction "1_1") (pintype "passive"))
      (node (ref "C14") (pin "1") (pinfunction "1_1") (pintype "passive"))
      (node (ref "C15") (pin "1") (pinfunction "1_1") (pintype "passive"))
      (node (ref "C18") (pin "+") (pinfunction "+_+") (pintype "passive"))
      (node (ref "L2") (pin "2") (pinfunction "2_2") (pintype "passive"))
      (node (ref "R4") (pin "1") (pinfunction "1_1") (pintype "passive"))
      (node (ref "R8") (pin "2") (pinfunction "2_2") (pintype "passive"))
      (node (ref "R9") (pin "2") (pinfunction "2_2") (pintype "passive"))
      (node (ref "U4") (pin "11") (pinfunction "AVDD_4_11") (pintype "power_in"))
      (node (ref "U4") (pin "15") (pinfunction "AVDD_5_15") (pintype "power_in"))
      (node (ref "U4") (pin "17") (pinfunction "AVDD_6_17") (pintype "power_in"))
      (node (ref "U4") (pin "21") (pinfunction "AVDD_21") (pintype "power_in"))
      (node (ref "U4") (pin "4") (pinfunction "AVDD_2_4") (pintype "power_in"))
      (node (ref "U4") (pin "8") (pinfunction "AVDD_3_8") (pintype "power_in"))
    )
    (net (code "74") (name "V5.0") (class "Default")
      (node (ref "C4") (pin "1") (pinfunction "1_1") (pintype "passive"))
      (node (ref "C5") (pin "2") (pinfunction "2_2") (pintype "passive"))
      (node (ref "U3") (pin "3") (pinfunction "OUT_3") (pintype "output"))
      (node (ref "U5") (pin "11") (pinfunction "VDD_11") (pintype "power_in"))
      (node (ref "U5") (pin "9") (pinfunction "BAT_9") (pintype "passive"))
    )
    (net (code "75") (name "VIN") (class "Default")
      (node (ref "C3") (pin "1") (pinfunction "1_1") (pintype "passive"))
      (node (ref "C32") (pin "+") (pinfunction "+_+") (pintype "passive"))
      (node (ref "D4") (pin "C") (pinfunction "C_C") (pintype "passive"))
      (node (ref "D5") (pin "C") (pinfunction "C_C") (pintype "passive"))
      (node (ref "U3") (pin "1") (pinfunction "IN_1") (pintype "input"))
    )
    (net (code "76") (name "unconnected-(G1-+-Pad+@1)") (class "Default")
      (node (ref "G1") (pin "+@1") (pinfunction "+_+@1") (pintype "passive"))
    )
    (net (code "77") (name "unconnected-(J3-Pad7)") (class "Default")
      (node (ref "J3") (pin "7") (pinfunction "7_7") (pintype "bidirectional"))
    )
    (net (code "78") (name "unconnected-(SV1-Pad5)") (class "Default")
      (node (ref "SV1") (pin "5") (pinfunction "5_5") (pintype "passive"))
    )
    (net (code "79") (name "unconnected-(SV1-Pad6)") (class "Default")
      (node (ref "SV1") (pin "6") (pinfunction "6_6") (pintype "passive"))
    )
    (net (code "80") (name "unconnected-(SV1-Pad7)") (class "Default")
      (node (ref "SV1") (pin "7") (pinfunction "7_7") (pintype "passive"))
    )
    (net (code "81") (name "unconnected-(SV1-Pad8)") (class "Default")
      (node (ref "SV1") (pin "8") (pinfunction "8_8") (pintype "passive"))
    )
    (net (code "82") (name "unconnected-(SV1-Pad9)") (class "Default")
      (node (ref "SV1") (pin "9") (pinfunction "9_9") (pintype "passive"))
    )
    (net (code "83") (name "unconnected-(SV1-Pad10)") (class "Default")
      (node (ref "SV1") (pin "10") (pinfunction "10_10") (pintype "passive"))
    )
    (net (code "84") (name "unconnected-(U1A-PA1-Pad11)") (class "Default")
      (node (ref "U1") (pin "11") (pinfunction "PA1_11") (pintype "bidirectional"))
    )
    (net (code "85") (name "unconnected-(U1A-PA2-Pad12)") (class "Default")
      (node (ref "U1") (pin "12") (pinfunction "PA2_12") (pintype "bidirectional"))
    )
    (net (code "86") (name "unconnected-(U1A-PA3-Pad13)") (class "Default")
      (node (ref "U1") (pin "13") (pinfunction "PA3_13") (pintype "bidirectional"))
    )
    (net (code "87") (name "unconnected-(U1A-PA4-Pad14)") (class "Default")
      (node (ref "U1") (pin "14") (pinfunction "PA4_14") (pintype "bidirectional"))
    )
    (net (code "88") (name "unconnected-(U1A-PA11-Pad32)") (class "Default")
      (node (ref "U1") (pin "32") (pinfunction "PA11_32") (pintype "bidirectional"))
    )
    (net (code "89") (name "unconnected-(U1A-PA12-Pad33)") (class "Default")
      (node (ref "U1") (pin "33") (pinfunction "PA12_33") (pintype "bidirectional"))
    )
    (net (code "90") (name "unconnected-(U1A-PB8-Pad45)") (class "Default")
      (node (ref "U1") (pin "45") (pinfunction "PB8_45") (pintype "bidirectional"))
    )
    (net (code "91") (name "unconnected-(U1A-PB9-Pad46)") (class "Default")
      (node (ref "U1") (pin "46") (pinfunction "PB9_46") (pintype "bidirectional"))
    )
    (net (code "92") (name "unconnected-(U1A-PB10-Pad21)") (class "Default")
      (node (ref "U1") (pin "21") (pinfunction "PB10_21") (pintype "bidirectional"))
    )
    (net (code "93") (name "unconnected-(U1A-PB12-Pad25)") (class "Default")
      (node (ref "U1") (pin "25") (pinfunction "PB12_25") (pintype "bidirectional"))
    )
    (net (code "94") (name "unconnected-(U1A-PB13-Pad26)") (class "Default")
      (node (ref "U1") (pin "26") (pinfunction "PB13_26") (pintype "bidirectional"))
    )
    (net (code "95") (name "unconnected-(U1A-PB14-Pad27)") (class "Default")
      (node (ref "U1") (pin "27") (pinfunction "PB14_27") (pintype "bidirectional"))
    )
    (net (code "96") (name "unconnected-(U1A-PB15-Pad28)") (class "Default")
      (node (ref "U1") (pin "28") (pinfunction "PB15_28") (pintype "bidirectional"))
    )
    (net (code "97") (name "unconnected-(U1A-PC13-Pad2)") (class "Default")
      (node (ref "U1") (pin "2") (pinfunction "PC13_2") (pintype "bidirectional"))
    )
    (net (code "98") (name "unconnected-(U4-DNC-Pad7)") (class "Default")
      (node (ref "U4") (pin "7") (pinfunction "DNC_7") (pintype "no_connect"))
    )
    (net (code "99") (name "unconnected-(U4-DUPLED-Pad26)") (class "Default")
      (node (ref "U4") (pin "26") (pinfunction "DUPLED_26") (pintype "passive"))
    )
    (net (code "100") (name "unconnected-(U4-NC-Pad47)") (class "Default")
      (node (ref "U4") (pin "47") (pinfunction "NC_47") (pintype "no_connect"))
    )
    (net (code "101") (name "unconnected-(U4-NC_2-Pad12)") (class "Default")
      (node (ref "U4") (pin "12") (pinfunction "NC_2_12") (pintype "no_connect"))
    )
    (net (code "102") (name "unconnected-(U4-NC_3-Pad13)") (class "Default")
      (node (ref "U4") (pin "13") (pinfunction "NC_3_13") (pintype "no_connect"))
    )
    (net (code "103") (name "unconnected-(U4-NC_4-Pad46)") (class "Default")
      (node (ref "U4") (pin "46") (pinfunction "NC_4_46") (pintype "no_connect"))
    )
    (net (code "104") (name "unconnected-(U4-RSVD-Pad42)") (class "Default")
      (node (ref "U4") (pin "42") (pinfunction "RSVD_42") (pintype "passive"))
    )
    (net (code "105") (name "unconnected-(U4-RSVD_2-Pad23)") (class "Default")
      (node (ref "U4") (pin "23") (pinfunction "RSVD_2_23") (pintype "passive"))
    )
    (net (code "106") (name "unconnected-(U4-RSVD_3-Pad38)") (class "Default")
      (node (ref "U4") (pin "38") (pinfunction "RSVD_3_38") (pintype "passive"))
    )
    (net (code "107") (name "unconnected-(U4-RSVD_4-Pad39)") (class "Default")
      (node (ref "U4") (pin "39") (pinfunction "RSVD_4_39") (pintype "passive"))
    )
    (net (code "108") (name "unconnected-(U4-RSVD_5-Pad40)") (class "Default")
      (node (ref "U4") (pin "40") (pinfunction "RSVD_5_40") (pintype "passive"))
    )
    (net (code "109") (name "unconnected-(U4-RSVD_6-Pad41)") (class "Default")
      (node (ref "U4") (pin "41") (pinfunction "RSVD_6_41") (pintype "passive"))
    )
    (net (code "110") (name "unconnected-(U4-SPDLED-Pad24)") (class "Default")
      (node (ref "U4") (pin "24") (pinfunction "SPDLED_24") (pintype "passive"))
    )
    (net (code "111") (name "unconnected-(U4-VBG-Pad18)") (class "Default")
      (node (ref "U4") (pin "18") (pinfunction "VBG_18") (pintype "passive"))
    )
    (net (code "112") (name "unconnected-(U5-PF-Pad5)") (class "Default")
      (node (ref "U5") (pin "5") (pinfunction "PF_5") (pintype "output"))
    )
    (net (code "113") (name "unconnected-(U5-TXI-Pad7)") (class "Default")
      (node (ref "U5") (pin "7") (pinfunction "TXI_7") (pintype "output"))
    )
    (net (code "114") (name "unconnected-(U5-VB-Pad2)") (class "Default")
      (node (ref "U5") (pin "2") (pinfunction "VB_2") (pintype "passive"))
    )
    (net (code "115") (name "unconnected-(U5-VS-Pad10)") (class "Default")
      (node (ref "U5") (pin "10") (pinfunction "VS_10") (pintype "passive"))
    )
  )
)
